# RadioShield.net
KiCad netlist of a schematic drawn in EAGLE
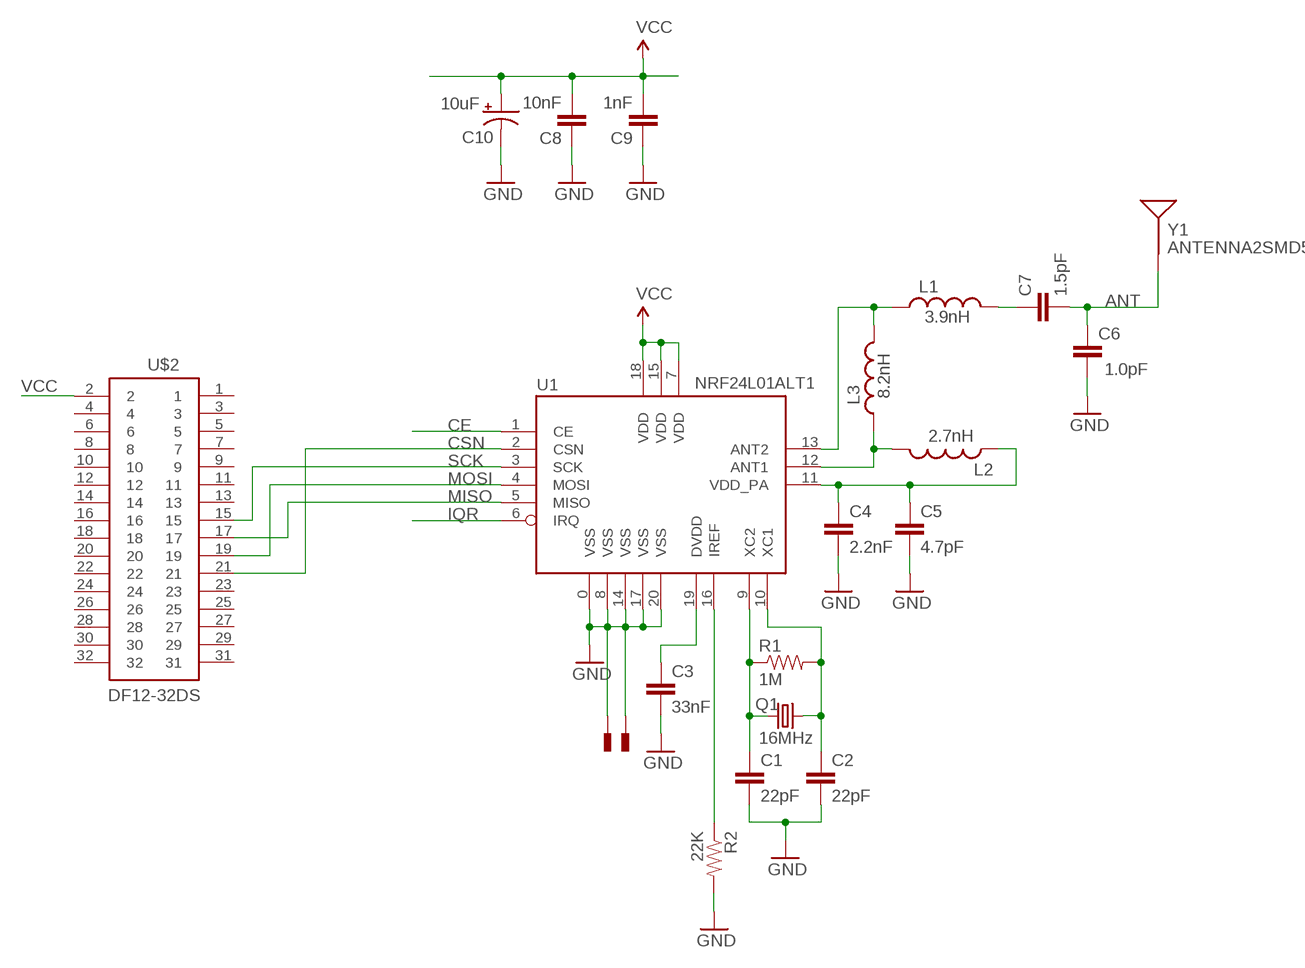
[diagram p0: schematic, sheet 1]

(export (version "E")
  (design (tool "Eeschema 10.0.6"))
  (components
    (comp (ref "C1")
      (value "22pF")
      (footprint "eagle-import:0402-CAP")
      (libsource (lib "eagle-import") (part "CAP0402-CAP"))
    )
    (comp (ref "C2")
      (value "22pF")
      (footprint "eagle-import:0402-CAP")
      (libsource (lib "eagle-import") (part "CAP0402-CAP"))
    )
    (comp (ref "C3")
      (value "33nF")
      (footprint "eagle-import:0402-CAP")
      (libsource (lib "eagle-import") (part "CAP0402-CAP"))
    )
    (comp (ref "C4")
      (value "2.2nF")
      (footprint "eagle-import:0402-CAP")
      (libsource (lib "eagle-import") (part "CAP0402-CAP"))
    )
    (comp (ref "C5")
      (value "4.7pF")
      (footprint "eagle-import:0402-CAP")
      (libsource (lib "eagle-import") (part "CAP0402-CAP"))
    )
    (comp (ref "C6")
      (value "1.0pF")
      (footprint "eagle-import:0402-CAP")
      (libsource (lib "eagle-import") (part "CAP0402-CAP"))
    )
    (comp (ref "C7")
      (value "1.5pF")
      (footprint "eagle-import:0402-CAP")
      (libsource (lib "eagle-import") (part "CAP0402-CAP"))
    )
    (comp (ref "C8")
      (value "10nF")
      (footprint "eagle-import:0402-CAP")
      (libsource (lib "eagle-import") (part "CAP0402-CAP"))
    )
    (comp (ref "C9")
      (value "1nF")
      (footprint "eagle-import:0402-CAP")
      (libsource (lib "eagle-import") (part "CAP0402-CAP"))
    )
    (comp (ref "C10")
      (value "10uF")
      (footprint "eagle-import:EIA3216")
      (libsource (lib "eagle-import") (part "CAP_POL1206"))
    )
    (comp (ref "L1")
      (value "3.9nH")
      (footprint "eagle-import:C0402")
      (libsource (lib "eagle-import") (part "INDUCTOR0402"))
    )
    (comp (ref "L2")
      (value "2.7nH")
      (footprint "eagle-import:C0402")
      (libsource (lib "eagle-import") (part "INDUCTOR0402"))
    )
    (comp (ref "L3")
      (value "8.2nH")
      (footprint "eagle-import:C0402")
      (libsource (lib "eagle-import") (part "INDUCTOR0402"))
    )
    (comp (ref "Q1")
      (value "16MHz")
      (footprint "eagle-import:CRYSTAL-SMD-5X3")
      (libsource (lib "eagle-import") (part "CRYSTAL5X3"))
    )
    (comp (ref "R1")
      (value "1M")
      (footprint "eagle-import:0402-RES")
      (libsource (lib "eagle-import") (part "RESISTOR0402-RES"))
    )
    (comp (ref "R2")
      (value "22K")
      (footprint "eagle-import:0402-RES")
      (libsource (lib "eagle-import") (part "RESISTOR0402-RES"))
    )
    (comp (ref "U$1")
      (value "PAD")
      (footprint "eagle-import:PAD-0.008")
      (libsource (lib "eagle-import") (part "PAD"))
    )
    (comp (ref "U$2")
      (value "HIROSE-DF12-32DSMALE")
      (footprint "eagle-import:DF12(3.0)-32DS-0.5V(86)-MALE")
      (libsource (lib "eagle-import") (part "HIROSE-DF12-32DSMALE"))
    )
    (comp (ref "U$4")
      (value "PAD")
      (footprint "eagle-import:PAD-0.008")
      (libsource (lib "eagle-import") (part "PAD"))
    )
    (comp (ref "U1")
      (value "NRF24L01ALT1")
      (footprint "eagle-import:QFN20_ALT1")
      (libsource (lib "eagle-import") (part "NRF24L01ALT1"))
    )
    (comp (ref "Y1")
      (value "ANTENNA2SMD5")
      (footprint "eagle-import:ANTENNA-CHIP5")
      (libsource (lib "eagle-import") (part "ANTENNA2SMD5"))
    )
  )
  (nets
    (net (code "1") (name "/ANT") (class "Default")
      (node (ref "C6") (pin "2") (pinfunction "2_2") (pintype "passive"))
      (node (ref "C7") (pin "2") (pinfunction "2_2") (pintype "passive"))
      (node (ref "Y1") (pin "FEED") (pinfunction "SIGNAL_FEED") (pintype "bidirectional"))
    )
    (net (code "2") (name "/CE") (class "Default")
      (node (ref "U1") (pin "1") (pinfunction "CE_1") (pintype "input"))
    )
    (net (code "3") (name "/CSN") (class "Default")
      (node (ref "U$2") (pin "21") (pinfunction "21_21") (pintype "bidirectional"))
      (node (ref "U1") (pin "2") (pinfunction "CSN_2") (pintype "input"))
    )
    (net (code "4") (name "/IQR") (class "Default")
      (node (ref "U1") (pin "6") (pinfunction "IRQ_6") (pintype "output"))
    )
    (net (code "5") (name "/MISO") (class "Default")
      (node (ref "U$2") (pin "17") (pinfunction "17_17") (pintype "bidirectional"))
      (node (ref "U1") (pin "5") (pinfunction "MISO_5") (pintype "output"))
    )
    (net (code "6") (name "/MOSI") (class "Default")
      (node (ref "U$2") (pin "19") (pinfunction "19_19") (pintype "bidirectional"))
      (node (ref "U1") (pin "4") (pinfunction "MOSI_4") (pintype "input"))
    )
    (net (code "7") (name "/SCK") (class "Default")
      (node (ref "U$2") (pin "15") (pinfunction "15_15") (pintype "bidirectional"))
      (node (ref "U1") (pin "3") (pinfunction "SCK_3") (pintype "input"))
    )
    (net (code "8") (name "GND") (class "Default")
      (node (ref "C1") (pin "2") (pinfunction "2_2") (pintype "passive"))
      (node (ref "C10") (pin "C") (pinfunction "-_C") (pintype "passive"))
      (node (ref "C2") (pin "2") (pinfunction "2_2") (pintype "passive"))
      (node (ref "C3") (pin "2") (pinfunction "2_2") (pintype "passive"))
      (node (ref "C4") (pin "2") (pinfunction "2_2") (pintype "passive"))
      (node (ref "C5") (pin "2") (pinfunction "2_2") (pintype "passive"))
      (node (ref "C6") (pin "1") (pinfunction "1_1") (pintype "passive"))
      (node (ref "C8") (pin "1") (pinfunction "1_1") (pintype "passive"))
      (node (ref "C9") (pin "1") (pinfunction "1_1") (pintype "passive"))
      (node (ref "R2") (pin "2") (pinfunction "2_2") (pintype "passive"))
      (node (ref "U$1") (pin "P$1") (pinfunction "P$1_P$1") (pintype "bidirectional"))
      (node (ref "U$4") (pin "P$1") (pinfunction "P$1_P$1") (pintype "bidirectional"))
      (node (ref "U1") (pin "0") (pinfunction "VSS_0") (pintype "power_in"))
      (node (ref "U1") (pin "14") (pinfunction "VSS_14") (pintype "power_in"))
      (node (ref "U1") (pin "17") (pinfunction "VSS_17") (pintype "power_in"))
      (node (ref "U1") (pin "20") (pinfunction "VSS_20") (pintype "power_in"))
      (node (ref "U1") (pin "8") (pinfunction "VSS_8") (pintype "power_in"))
    )
    (net (code "9") (name "Net-(C7-Pad1)") (class "Default")
      (node (ref "C7") (pin "1") (pinfunction "1_1") (pintype "passive"))
      (node (ref "L1") (pin "2") (pinfunction "2_2") (pintype "passive"))
    )
    (net (code "10") (name "Net-(Q1-2)") (class "Default")
      (node (ref "C2") (pin "1") (pinfunction "1_1") (pintype "passive"))
      (node (ref "Q1") (pin "3") (pinfunction "2_3") (pintype "passive"))
      (node (ref "R1") (pin "2") (pinfunction "2_2") (pintype "passive"))
      (node (ref "U1") (pin "10") (pinfunction "XC1_10") (pintype "input"))
    )
    (net (code "11") (name "Net-(U1-ANT1)") (class "Default")
      (node (ref "L2") (pin "2") (pinfunction "2_2") (pintype "passive"))
      (node (ref "L3") (pin "1") (pinfunction "1_1") (pintype "passive"))
      (node (ref "U1") (pin "12") (pinfunction "ANT1_12") (pintype "output"))
    )
    (net (code "12") (name "Net-(U1-ANT2)") (class "Default")
      (node (ref "L1") (pin "1") (pinfunction "1_1") (pintype "passive"))
      (node (ref "L3") (pin "2") (pinfunction "2_2") (pintype "passive"))
      (node (ref "U1") (pin "13") (pinfunction "ANT2_13") (pintype "output"))
    )
    (net (code "13") (name "Net-(U1-DVDD)") (class "Default")
      (node (ref "C3") (pin "1") (pinfunction "1_1") (pintype "passive"))
      (node (ref "U1") (pin "19") (pinfunction "DVDD_19") (pintype "power_in"))
    )
    (net (code "14") (name "Net-(U1-IREF)") (class "Default")
      (node (ref "R2") (pin "1") (pinfunction "1_1") (pintype "passive"))
      (node (ref "U1") (pin "16") (pinfunction "IREF_16") (pintype "input"))
    )
    (net (code "15") (name "Net-(U1-VDD_PA)") (class "Default")
      (node (ref "C4") (pin "1") (pinfunction "1_1") (pintype "passive"))
      (node (ref "C5") (pin "1") (pinfunction "1_1") (pintype "passive"))
      (node (ref "L2") (pin "1") (pinfunction "1_1") (pintype "passive"))
      (node (ref "U1") (pin "11") (pinfunction "VDD_PA_11") (pintype "power_in"))
    )
    (net (code "16") (name "Net-(U1-XC2)") (class "Default")
      (node (ref "C1") (pin "1") (pinfunction "1_1") (pintype "passive"))
      (node (ref "Q1") (pin "1") (pinfunction "1_1") (pintype "passive"))
      (node (ref "R1") (pin "1") (pinfunction "1_1") (pintype "passive"))
      (node (ref "U1") (pin "9") (pinfunction "XC2_9") (pintype "input"))
    )
    (net (code "17") (name "VCC") (class "Default")
      (node (ref "C10") (pin "A") (pinfunction "+_A") (pintype "passive"))
      (node (ref "C8") (pin "2") (pinfunction "2_2") (pintype "passive"))
      (node (ref "C9") (pin "2") (pinfunction "2_2") (pintype "passive"))
      (node (ref "U$2") (pin "2") (pinfunction "2_2") (pintype "bidirectional"))
      (node (ref "U1") (pin "15") (pinfunction "VDD_15") (pintype "power_in"))
      (node (ref "U1") (pin "18") (pinfunction "VDD_18") (pintype "power_in"))
      (node (ref "U1") (pin "7") (pinfunction "VDD_7") (pintype "power_in"))
    )
    (net (code "18") (name "unconnected-(U$2-Pad1)") (class "Default")
      (node (ref "U$2") (pin "1") (pinfunction "1_1") (pintype "bidirectional"))
    )
    (net (code "19") (name "unconnected-(U$2-Pad3)") (class "Default")
      (node (ref "U$2") (pin "3") (pinfunction "3_3") (pintype "bidirectional"))
    )
    (net (code "20") (name "unconnected-(U$2-Pad4)") (class "Default")
      (node (ref "U$2") (pin "4") (pinfunction "4_4") (pintype "bidirectional"))
    )
    (net (code "21") (name "unconnected-(U$2-Pad5)") (class "Default")
      (node (ref "U$2") (pin "5") (pinfunction "5_5") (pintype "bidirectional"))
    )
    (net (code "22") (name "unconnected-(U$2-Pad6)") (class "Default")
      (node (ref "U$2") (pin "6") (pinfunction "6_6") (pintype "bidirectional"))
    )
    (net (code "23") (name "unconnected-(U$2-Pad7)") (class "Default")
      (node (ref "U$2") (pin "7") (pinfunction "7_7") (pintype "bidirectional"))
    )
    (net (code "24") (name "unconnected-(U$2-Pad8)") (class "Default")
      (node (ref "U$2") (pin "8") (pinfunction "8_8") (pintype "bidirectional"))
    )
    (net (code "25") (name "unconnected-(U$2-Pad9)") (class "Default")
      (node (ref "U$2") (pin "9") (pinfunction "9_9") (pintype "bidirectional"))
    )
    (net (code "26") (name "unconnected-(U$2-Pad10)") (class "Default")
      (node (ref "U$2") (pin "10") (pinfunction "10_10") (pintype "bidirectional"))
    )
    (net (code "27") (name "unconnected-(U$2-Pad11)") (class "Default")
      (node (ref "U$2") (pin "11") (pinfunction "11_11") (pintype "bidirectional"))
    )
    (net (code "28") (name "unconnected-(U$2-Pad12)") (class "Default")
      (node (ref "U$2") (pin "12") (pinfunction "12_12") (pintype "bidirectional"))
    )
    (net (code "29") (name "unconnected-(U$2-Pad13)") (class "Default")
      (node (ref "U$2") (pin "13") (pinfunction "13_13") (pintype "bidirectional"))
    )
    (net (code "30") (name "unconnected-(U$2-Pad14)") (class "Default")
      (node (ref "U$2") (pin "14") (pinfunction "14_14") (pintype "bidirectional"))
    )
    (net (code "31") (name "unconnected-(U$2-Pad16)") (class "Default")
      (node (ref "U$2") (pin "16") (pinfunction "16_16") (pintype "bidirectional"))
    )
    (net (code "32") (name "unconnected-(U$2-Pad18)") (class "Default")
      (node (ref "U$2") (pin "18") (pinfunction "18_18") (pintype "bidirectional"))
    )
    (net (code "33") (name "unconnected-(U$2-Pad20)") (class "Default")
      (node (ref "U$2") (pin "20") (pinfunction "20_20") (pintype "bidirectional"))
    )
    (net (code "34") (name "unconnected-(U$2-Pad22)") (class "Default")
      (node (ref "U$2") (pin "22") (pinfunction "22_22") (pintype "bidirectional"))
    )
    (net (code "35") (name "unconnected-(U$2-Pad23)") (class "Default")
      (node (ref "U$2") (pin "23") (pinfunction "23_23") (pintype "bidirectional"))
    )
    (net (code "36") (name "unconnected-(U$2-Pad24)") (class "Default")
      (node (ref "U$2") (pin "24") (pinfunction "24_24") (pintype "bidirectional"))
    )
    (net (code "37") (name "unconnected-(U$2-Pad25)") (class "Default")
      (node (ref "U$2") (pin "25") (pinfunction "25_25") (pintype "bidirectional"))
    )
    (net (code "38") (name "unconnected-(U$2-Pad26)") (class "Default")
      (node (ref "U$2") (pin "26") (pinfunction "26_26") (pintype "bidirectional"))
    )
    (net (code "39") (name "unconnected-(U$2-Pad27)") (class "Default")
      (node (ref "U$2") (pin "27") (pinfunction "27_27") (pintype "bidirectional"))
    )
    (net (code "40") (name "unconnected-(U$2-Pad28)") (class "Default")
      (node (ref "U$2") (pin "28") (pinfunction "28_28") (pintype "bidirectional"))
    )
    (net (code "41") (name "unconnected-(U$2-Pad29)") (class "Default")
      (node (ref "U$2") (pin "29") (pinfunction "29_29") (pintype "bidirectional"))
    )
    (net (code "42") (name "unconnected-(U$2-Pad30)") (class "Default")
      (node (ref "U$2") (pin "30") (pinfunction "30_30") (pintype "bidirectional"))
    )
    (net (code "43") (name "unconnected-(U$2-Pad31)") (class "Default")
      (node (ref "U$2") (pin "31") (pinfunction "31_31") (pintype "bidirectional"))
    )
    (net (code "44") (name "unconnected-(U$2-Pad32)") (class "Default")
      (node (ref "U$2") (pin "32") (pinfunction "32_32") (pintype "bidirectional"))
    )
  )
)
